# drive_circuit.net
KiCad netlist of a schematic drawn in Altium Designer
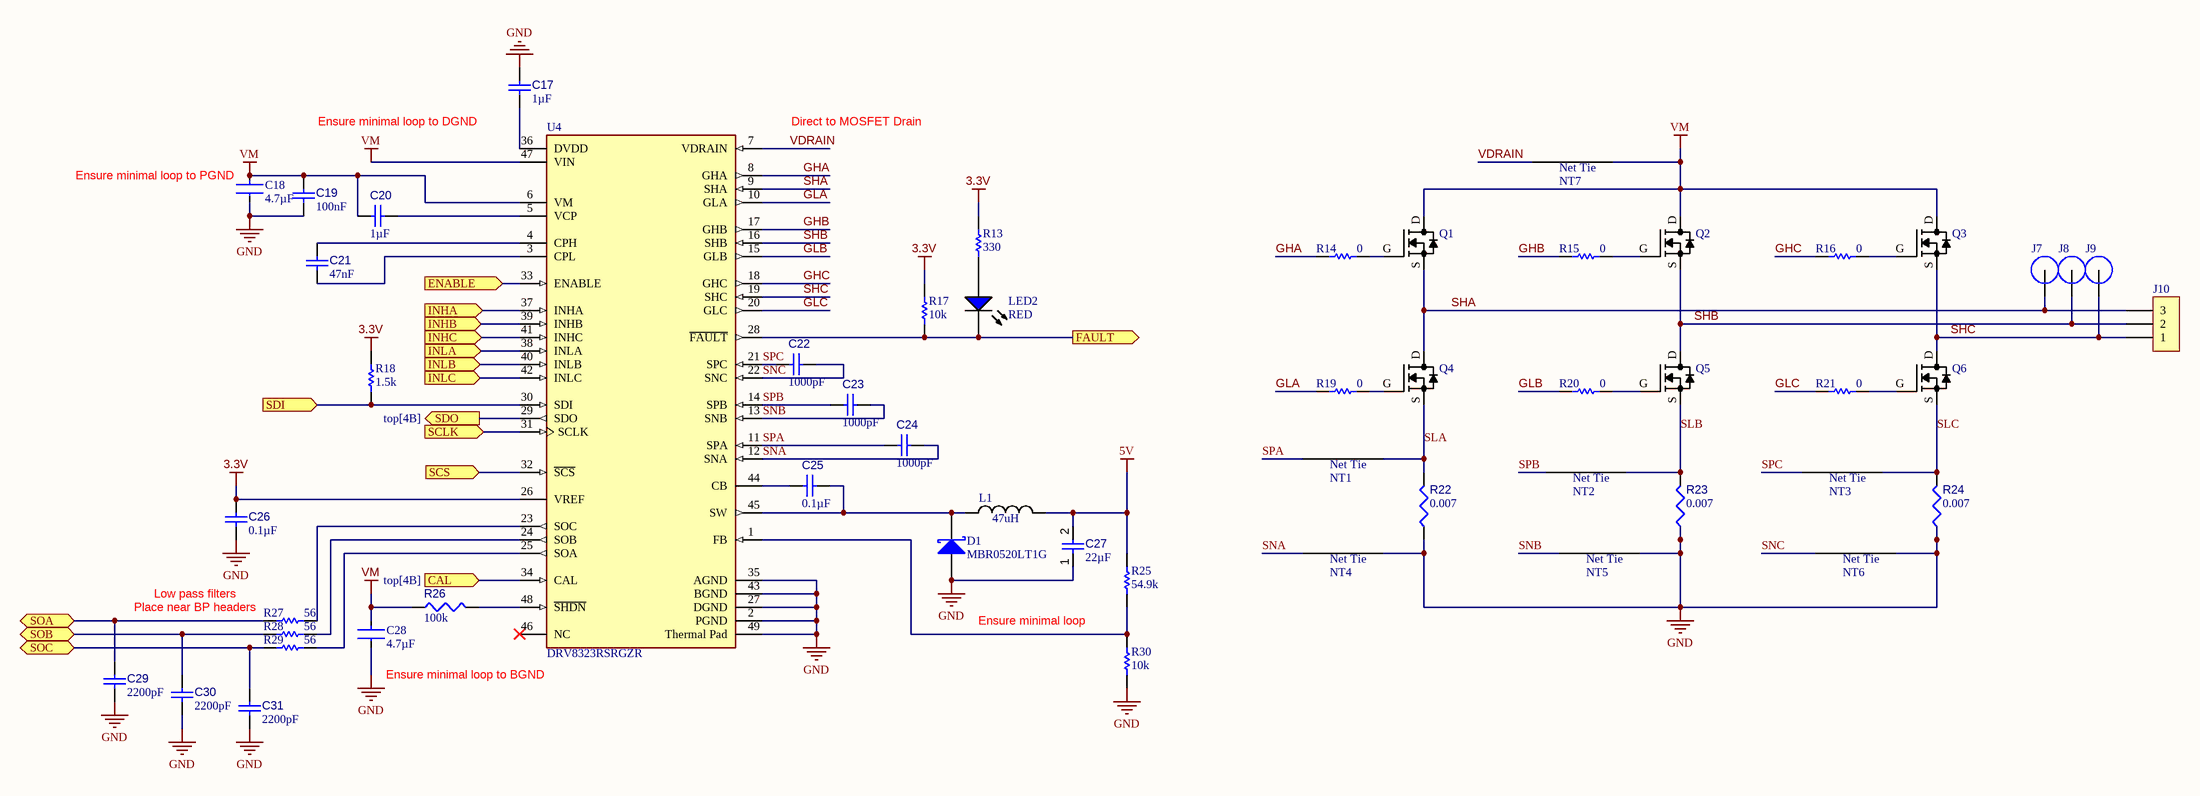
[diagram p0: drive_circuit.SchDoc]

(export (version "E")
  (design (tool "Eeschema 10.0.6"))
  (components
    (comp (ref "C17")
      (value "1µF")
      (footprint "CAPC1608X94X35NL15T15")
      (description "Chip Capacitor, 1 uF, +/- 10%, 6.3 V, 0603 (1608 Metric)")
      (fields (field (name "TOLERANCE") "10%") (field (name "Comment") "Capacitor 1 uF +/- 10% 16 V 0603"))
      (libsource (lib "bai yaohui") (part "CAP-NP-2"))
    )
    (comp (ref "C18")
      (value "4.7µF")
      (footprint "FP-MK325N-MFG")
      (fields (field (name "Comment") "HMK325B7225KN-T"))
      (libsource (lib "bai yaohui") (part "b4654b650e69147ec39a6b967a45e02"))
    )
    (comp (ref "C19")
      (value "100nF")
      (footprint "CAPC0603(1608)100_L")
      (description "Chip Capacitor, 4.7µF +/-20%, 100V, 0603, Thickness 1 mm")
      (fields (field (name "TOLERANCE") "10%") (field (name "Comment") "Capacitor 4.7µF +/-20% 10V 0603"))
      (libsource (lib "bai yaohui") (part "CAP-NP-2"))
    )
    (comp (ref "C20")
      (value "1µF")
      (footprint "CAPC1608X94X35NL15T15")
      (description "Chip Capacitor, 1 uF, +/- 10%, 16 V, 0603 (1608 Metric)")
      (fields (field (name "TOLERANCE") "10%") (field (name "Comment") "Capacitor 1 uF +/- 10% 16 V 0603"))
      (libsource (lib "bai yaohui") (part "CAP-NP-2"))
    )
    (comp (ref "C21")
      (value "47nF")
      (footprint "CAPC0603(1608)100_L")
      (description "Chip Capacitor, 47nF +/-20%, 100V, 0603, Thickness 1 mm")
      (fields (field (name "TOLERANCE") "10%") (field (name "Comment") "Capacitor 4.7µF +/-20% 10V 0603"))
      (libsource (lib "bai yaohui") (part "CAP-NP-2"))
    )
    (comp (ref "C22")
      (value "1000pF")
      (footprint "CAPC1608X94X35NL15T15")
      (description "Chip Capacitor, 0.1uF, +/- 10%, 6.3 V, 0603 (1608 Metric)")
      (fields (field (name "TOLERANCE") "10%") (field (name "Comment") "Capacitor 1 uF +/- 10% 16 V 0603"))
      (libsource (lib "bai yaohui") (part "CAP-NP-2"))
    )
    (comp (ref "C23")
      (value "1000pF")
      (footprint "CAPC1608X94X35NL15T15")
      (description "Chip Capacitor, 0.1uF, +/- 10%, 6.3 V, 0603 (1608 Metric)")
      (fields (field (name "TOLERANCE") "10%") (field (name "Comment") "Capacitor 1 uF +/- 10% 16 V 0603"))
      (libsource (lib "bai yaohui") (part "CAP-NP-2"))
    )
    (comp (ref "C24")
      (value "1000pF")
      (footprint "CAPC1608X94X35NL15T15")
      (description "Chip Capacitor, 0.1uF, +/- 10%, 6.3 V, 0603 (1608 Metric)")
      (fields (field (name "TOLERANCE") "10%") (field (name "Comment") "Capacitor 1 uF +/- 10% 16 V 0603"))
      (libsource (lib "bai yaohui") (part "CAP-NP-2"))
    )
    (comp (ref "C25")
      (value "0.1µF")
      (footprint "CAPC1608X94X35NL15T15")
      (description "Chip Capacitor, 0.1uF, +/- 10%, 6.3 V, 0603 (1608 Metric)")
      (fields (field (name "TOLERANCE") "10%") (field (name "Comment") "Capacitor 1 uF +/- 10% 16 V 0603"))
      (libsource (lib "bai yaohui") (part "CAP-NP-2"))
    )
    (comp (ref "C26")
      (value "0.1µF")
      (footprint "CAPC1608X94X35NL15T15")
      (description "Chip Capacitor, 0.1uF, +/- 10%, 6.3 V, 0603 (1608 Metric)")
      (fields (field (name "TOLERANCE") "10%") (field (name "Comment") "Capacitor 1 uF +/- 10% 16 V 0603"))
      (libsource (lib "bai yaohui") (part "CAP-NP-2"))
    )
    (comp (ref "C27")
      (value "22µF")
      (footprint "CAPC3216X180X50NL20T25")
      (description "Chip Capacitor, 22 uF, +/- 10%, 16 V, 1206 (3216 Metric)")
      (fields (field (name "TOLERANCE") "10%") (field (name "Comment") "Capacitor 10 uF +/- 10% 16 V 1206"))
      (libsource (lib "") (part "CAP-NP-2_1"))
    )
    (comp (ref "C28")
      (value "4.7µF")
      (footprint "FP-MK325N-MFG")
      (fields (field (name "Comment") "HMK325B7225KN-T"))
      (libsource (lib "bai yaohui") (part "b4654b650e69147ec39a6b967a45e02"))
    )
    (comp (ref "C29")
      (value "2200pF")
      (footprint "CAPC1608X94X35NL15T15")
      (description "Chip Capacitor, 0.1uF, +/- 10%, 6.3 V, 0603 (1608 Metric)")
      (fields (field (name "TOLERANCE") "10%") (field (name "Comment") "Capacitor 1 uF +/- 10% 16 V 0603"))
      (libsource (lib "bai yaohui") (part "CAP-NP-2"))
    )
    (comp (ref "C30")
      (value "2200pF")
      (footprint "CAPC1608X94X35NL15T15")
      (description "Chip Capacitor, 0.1uF, +/- 10%, 6.3 V, 0603 (1608 Metric)")
      (fields (field (name "TOLERANCE") "10%") (field (name "Comment") "Capacitor 1 uF +/- 10% 16 V 0603"))
      (libsource (lib "bai yaohui") (part "CAP-NP-2"))
    )
    (comp (ref "C31")
      (value "2200pF")
      (footprint "CAPC1608X94X35NL15T15")
      (description "Chip Capacitor, 0.1uF, +/- 10%, 6.3 V, 0603 (1608 Metric)")
      (fields (field (name "TOLERANCE") "10%") (field (name "Comment") "Capacitor 1 uF +/- 10% 16 V 0603"))
      (libsource (lib "bai yaohui") (part "CAP-NP-2"))
    )
    (comp (ref "D1")
      (value "MBR0520LT1G")
      (footprint "ONSC-SOD-123-2-425-04_V")
      (description "Schottky Power Rectifier, 20 V, 5.5 A, -65 to 125 degC, 2-Pin SMD, RoHS, Tape and Reel")
      (fields (field (name "MANUFACTURER") "ON Semiconductor"))
      (libsource (lib "bai yaohui") (part "DSKY-AK-2"))
    )
    (comp (ref "J7")
      (value "~")
      (footprint "M3 Spade Hole")
      (description "M3 Spade Terminal")
      (libsource (lib "CustomComponents") (part "M3 Spade Terminal"))
    )
    (comp (ref "J8")
      (value "~")
      (footprint "M3 Spade Hole")
      (description "M3 Spade Terminal")
      (libsource (lib "CustomComponents") (part "M3 Spade Terminal"))
    )
    (comp (ref "J9")
      (value "~")
      (footprint "M3 Spade Hole")
      (description "M3 Spade Terminal")
      (libsource (lib "CustomComponents") (part "M3 Spade Terminal"))
    )
    (comp (ref "J10")
      (value "1704936")
      (footprint "1704936")
      (description "CONN TERM BLOCK 3POS 7.62MM")
      (fields (field (name "MANUFACTURER") "Phoenix Contact") (field (name "VOLTAGE") "300V"))
      (libsource (lib "CustomComponents") (part "1704936"))
    )
    (comp (ref "L1")
      (value "47uH")
      (footprint "INDC6060X28N")
      (description "INDUCTOR 47UH 1.4A 175.5 MOHM")
      (fields (field (name "Comment") "22uH"))
      (libsource (lib "CustomComponents") (part "NR6028T220M"))
    )
    (comp (ref "LED2")
      (value "RED")
      (footprint "VISH-TLMX1100-2_V")
      (description "red LED, 10 mA, 2 V, -40 to 100 degC, 2-Pin SMD (0603), RoHS, Tape and Reel")
      (fields (field (name "POWER") "68mW") (field (name "MANUFACTURER") "Vishay Semiconductor"))
      (libsource (lib "bai yaohui") (part "LED-BLUE-AK-2"))
    )
    (comp (ref "NT1")
      (value "0.25mm")
      (footprint "CustomFootprints:NetTie_0.25mm")
      (libsource (lib "CustomComponents") (part "NetTie_0.25mm"))
    )
    (comp (ref "NT2")
      (value "0.25mm")
      (footprint "CustomFootprints:NetTie_0.25mm")
      (libsource (lib "CustomComponents") (part "NetTie_0.25mm"))
    )
    (comp (ref "NT3")
      (value "0.25mm")
      (footprint "CustomFootprints:NetTie_0.25mm")
      (libsource (lib "CustomComponents") (part "NetTie_0.25mm"))
    )
    (comp (ref "NT4")
      (value "0.25mm")
      (footprint "CustomFootprints:NetTie_0.25mm")
      (libsource (lib "CustomComponents") (part "NetTie_0.25mm"))
    )
    (comp (ref "NT5")
      (value "0.25mm")
      (footprint "CustomFootprints:NetTie_0.25mm")
      (libsource (lib "CustomComponents") (part "NetTie_0.25mm"))
    )
    (comp (ref "NT6")
      (value "0.25mm")
      (footprint "CustomFootprints:NetTie_0.25mm")
      (libsource (lib "CustomComponents") (part "NetTie_0.25mm"))
    )
    (comp (ref "NT7")
      (value "0.25mm")
      (footprint "CustomFootprints:NetTie_0.25mm")
      (libsource (lib "CustomComponents") (part "NetTie_0.25mm"))
    )
    (comp (ref "Q1")
      (value "~")
      (footprint "SO8FL")
      (description "MOSFET N-CH 30V 13A SO8FL")
      (fields
        (field (name "MANUFACTURER") "ON Semiconductor")
        (field (name "MANUFACTURER PART NUMBER") "NTMFS4935NT1G")
      )
      (libsource (lib "CustomComponents") (part "NTMFS4935NT1G"))
    )
    (comp (ref "Q2")
      (value "~")
      (footprint "SO8FL")
      (description "MOSFET N-CH 30V 13A SO8FL")
      (fields
        (field (name "MANUFACTURER") "ON Semiconductor")
        (field (name "MANUFACTURER PART NUMBER") "NTMFS4935NT1G")
      )
      (libsource (lib "CustomComponents") (part "NTMFS4935NT1G"))
    )
    (comp (ref "Q3")
      (value "~")
      (footprint "SO8FL")
      (description "MOSFET N-CH 30V 13A SO8FL")
      (fields
        (field (name "MANUFACTURER") "ON Semiconductor")
        (field (name "MANUFACTURER PART NUMBER") "NTMFS4935NT1G")
      )
      (libsource (lib "CustomComponents") (part "NTMFS4935NT1G"))
    )
    (comp (ref "Q4")
      (value "~")
      (footprint "SO8FL")
      (description "MOSFET N-CH 30V 13A SO8FL")
      (fields
        (field (name "MANUFACTURER") "ON Semiconductor")
        (field (name "MANUFACTURER PART NUMBER") "NTMFS4935NT1G")
      )
      (libsource (lib "CustomComponents") (part "NTMFS4935NT1G"))
    )
    (comp (ref "Q5")
      (value "~")
      (footprint "SO8FL")
      (description "MOSFET N-CH 30V 13A SO8FL")
      (fields
        (field (name "MANUFACTURER") "ON Semiconductor")
        (field (name "MANUFACTURER PART NUMBER") "NTMFS4935NT1G")
      )
      (libsource (lib "CustomComponents") (part "NTMFS4935NT1G"))
    )
    (comp (ref "Q6")
      (value "~")
      (footprint "SO8FL")
      (description "MOSFET N-CH 30V 13A SO8FL")
      (fields
        (field (name "MANUFACTURER") "ON Semiconductor")
        (field (name "MANUFACTURER PART NUMBER") "NTMFS4935NT1G")
      )
      (libsource (lib "CustomComponents") (part "NTMFS4935NT1G"))
    )
    (comp (ref "R13")
      (value "330")
      (footprint "RESC1608X55X25ML10T15")
      (description "Chip Resistor, 330 Ohm, 0.1 W, -55 to 155 degC, 0603 (1608 Metric)")
      (fields (field (name "POWER") "100mW") (field (name "TOLERANCE") "5%"))
      (libsource (lib "") (part "RES-2_1"))
    )
    (comp (ref "R14")
      (value "0")
      (footprint "RESC1608X55X25ML10T15")
      (description "Chip Resistor, 10k Ohm, 0.1 W, -55 to 155 degC, 0603 (1608 Metric)")
      (fields (field (name "POWER") "100mW") (field (name "TOLERANCE") "5%"))
      (libsource (lib "") (part "RES-2_1"))
    )
    (comp (ref "R15")
      (value "0")
      (footprint "RESC1608X55X25ML10T15")
      (description "Chip Resistor, 10k Ohm, 0.1 W, -55 to 155 degC, 0603 (1608 Metric)")
      (fields (field (name "POWER") "100mW") (field (name "TOLERANCE") "5%"))
      (libsource (lib "") (part "RES-2_1"))
    )
    (comp (ref "R16")
      (value "0")
      (footprint "RESC1608X55X25ML10T15")
      (description "Chip Resistor, 10k Ohm, 0.1 W, -55 to 155 degC, 0603 (1608 Metric)")
      (fields (field (name "POWER") "100mW") (field (name "TOLERANCE") "5%"))
      (libsource (lib "") (part "RES-2_1"))
    )
    (comp (ref "R17")
      (value "10k")
      (footprint "RESC1608X55X25ML10T15")
      (description "Chip Resistor, 10k Ohm, 0.1 W, -55 to 155 degC, 0603 (1608 Metric)")
      (fields (field (name "POWER") "100mW") (field (name "TOLERANCE") "5%"))
      (libsource (lib "") (part "RES-2_1"))
    )
    (comp (ref "R18")
      (value "1.5k")
      (footprint "RESC1608X55X25ML10T15")
      (description "Chip Resistor, 1.5k Ohm, 0.1 W, -55 to 155 degC, 0603 (1608 Metric)")
      (fields (field (name "POWER") "100mW") (field (name "TOLERANCE") "5%"))
      (libsource (lib "") (part "RES-2_1"))
    )
    (comp (ref "R19")
      (value "0")
      (footprint "RESC1608X55X25ML10T15")
      (description "Chip Resistor, 10k Ohm, 0.1 W, -55 to 155 degC, 0603 (1608 Metric)")
      (fields (field (name "POWER") "100mW") (field (name "TOLERANCE") "5%"))
      (libsource (lib "") (part "RES-2_1"))
    )
    (comp (ref "R20")
      (value "0")
      (footprint "RESC1608X55X25ML10T15")
      (description "Chip Resistor, 10k Ohm, 0.1 W, -55 to 155 degC, 0603 (1608 Metric)")
      (fields (field (name "POWER") "100mW") (field (name "TOLERANCE") "5%"))
      (libsource (lib "") (part "RES-2_1"))
    )
    (comp (ref "R21")
      (value "0")
      (footprint "RESC1608X55X25ML10T15")
      (description "Chip Resistor, 10k Ohm, 0.1 W, -55 to 155 degC, 0603 (1608 Metric)")
      (fields (field (name "POWER") "100mW") (field (name "TOLERANCE") "5%"))
      (libsource (lib "") (part "RES-2_1"))
    )
    (comp (ref "R22")
      (value "0.007")
      (footprint "FP-RT2512-MFG")
      (description "Fixed Resistor, Thin Film, 0.75W, 1210ohm, 200V, 0.1% +/-Tol, 25ppm/Cel, Surface Mount, 2512")
      (fields (field (name "POWER") "750mW") (field (name "TOLERANCE") "0.1%"))
      (libsource (lib "bai yaohui") (part "RES-2"))
    )
    (comp (ref "R23")
      (value "0.007")
      (footprint "FP-RT2512-MFG")
      (description "Fixed Resistor, Thin Film, 0.75W, 1210ohm, 200V, 0.1% +/-Tol, 25ppm/Cel, Surface Mount, 2512")
      (fields (field (name "POWER") "750mW") (field (name "TOLERANCE") "0.1%"))
      (libsource (lib "bai yaohui") (part "RES-2"))
    )
    (comp (ref "R24")
      (value "0.007")
      (footprint "FP-RT2512-MFG")
      (description "Fixed Resistor, Thin Film, 0.75W, 1210ohm, 200V, 0.1% +/-Tol, 25ppm/Cel, Surface Mount, 2512")
      (fields (field (name "POWER") "750mW") (field (name "TOLERANCE") "0.1%"))
      (libsource (lib "bai yaohui") (part "RES-2"))
    )
    (comp (ref "R25")
      (value "54.9k")
      (footprint "RESC1608X55X25ML10T15")
      (description "Chip Resistor, 10k Ohm, 0.1 W, -55 to 155 degC, 0603 (1608 Metric)")
      (fields (field (name "POWER") "100mW") (field (name "TOLERANCE") "5%"))
      (libsource (lib "") (part "RES-2_1"))
    )
    (comp (ref "R26")
      (value "100k")
      (footprint "RESC1608X55X25ML10T15")
      (description "Chip Resistor, 100 KOhm, +/- 1%, 0.1 W, -55 to 155 degC, 0603 (1608 Metric)")
      (fields (field (name "TOLERANCE") "1%") (field (name "POWER") "100mW"))
      (libsource (lib "bai yaohui") (part "RES-2"))
    )
    (comp (ref "R27")
      (value "56")
      (footprint "RESC1608X55X25ML10T15")
      (description "Chip Resistor, 10k Ohm, 0.1 W, -55 to 155 degC, 0603 (1608 Metric)")
      (fields (field (name "POWER") "100mW") (field (name "TOLERANCE") "5%"))
      (libsource (lib "") (part "RES-2_1"))
    )
    (comp (ref "R28")
      (value "56")
      (footprint "RESC1608X55X25ML10T15")
      (description "Chip Resistor, 10k Ohm, 0.1 W, -55 to 155 degC, 0603 (1608 Metric)")
      (fields (field (name "POWER") "100mW") (field (name "TOLERANCE") "5%"))
      (libsource (lib "") (part "RES-2_1"))
    )
    (comp (ref "R29")
      (value "56")
      (footprint "RESC1608X55X25ML10T15")
      (description "Chip Resistor, 10k Ohm, 0.1 W, -55 to 155 degC, 0603 (1608 Metric)")
      (fields (field (name "POWER") "100mW") (field (name "TOLERANCE") "5%"))
      (libsource (lib "") (part "RES-2_1"))
    )
    (comp (ref "R30")
      (value "10k")
      (footprint "RESC1608X55X25ML10T15")
      (description "Chip Resistor, 10k Ohm, 0.1 W, -55 to 155 degC, 0603 (1608 Metric)")
      (fields (field (name "POWER") "100mW") (field (name "TOLERANCE") "5%"))
      (libsource (lib "") (part "RES-2_1"))
    )
    (comp (ref "U4")
      (value "DRV8323RSRGZR")
      (footprint "FP-RGZ0048A-IPC_A")
      (description "Brushless DC Motor Controller, 0.005A, PQCC48")
      (libsource (lib "bai yaohui") (part "9f6f2f4cce60835f155f5fba280b04a"))
    )
  )
  (nets
    (net (code "1") (name "/CAL") (class "Default")
      (node (ref "U4") (pin "34") (pinfunction "CAL_34") (pintype "input"))
    )
    (net (code "2") (name "/ENABLE") (class "Default")
      (node (ref "U4") (pin "33") (pinfunction "ENABLE_33") (pintype "input"))
    )
    (net (code "3") (name "/FAULT") (class "Default")
      (node (ref "LED2") (pin "2") (pinfunction "K_2") (pintype "passive"))
      (node (ref "R17") (pin "1") (pinfunction "1_1") (pintype "passive"))
      (node (ref "U4") (pin "28") (pinfunction "~{FAULT}_28") (pintype "output"))
    )
    (net (code "4") (name "/GHA") (class "Default")
      (node (ref "R14") (pin "2") (pinfunction "2_2") (pintype "passive"))
      (node (ref "U4") (pin "8") (pinfunction "GHA_8") (pintype "output"))
    )
    (net (code "5") (name "/GHB") (class "Default")
      (node (ref "R15") (pin "2") (pinfunction "2_2") (pintype "passive"))
      (node (ref "U4") (pin "17") (pinfunction "GHB_17") (pintype "output"))
    )
    (net (code "6") (name "/GHC") (class "Default")
      (node (ref "R16") (pin "2") (pinfunction "2_2") (pintype "passive"))
      (node (ref "U4") (pin "18") (pinfunction "GHC_18") (pintype "output"))
    )
    (net (code "7") (name "/GLA") (class "Default")
      (node (ref "R19") (pin "2") (pinfunction "2_2") (pintype "passive"))
      (node (ref "U4") (pin "10") (pinfunction "GLA_10") (pintype "output"))
    )
    (net (code "8") (name "/GLB") (class "Default")
      (node (ref "R20") (pin "2") (pinfunction "2_2") (pintype "passive"))
      (node (ref "U4") (pin "15") (pinfunction "GLB_15") (pintype "output"))
    )
    (net (code "9") (name "/GLC") (class "Default")
      (node (ref "R21") (pin "2") (pinfunction "2_2") (pintype "passive"))
      (node (ref "U4") (pin "20") (pinfunction "GLC_20") (pintype "output"))
    )
    (net (code "10") (name "/INHA") (class "Default")
      (node (ref "U4") (pin "37") (pinfunction "INHA_37") (pintype "input"))
    )
    (net (code "11") (name "/INHB") (class "Default")
      (node (ref "U4") (pin "39") (pinfunction "INHB_39") (pintype "input"))
    )
    (net (code "12") (name "/INHC") (class "Default")
      (node (ref "U4") (pin "41") (pinfunction "INHC_41") (pintype "input"))
    )
    (net (code "13") (name "/INLA") (class "Default")
      (node (ref "U4") (pin "38") (pinfunction "INLA_38") (pintype "input"))
    )
    (net (code "14") (name "/INLB") (class "Default")
      (node (ref "U4") (pin "40") (pinfunction "INLB_40") (pintype "input"))
    )
    (net (code "15") (name "/INLC") (class "Default")
      (node (ref "U4") (pin "42") (pinfunction "INLC_42") (pintype "input"))
    )
    (net (code "16") (name "/SCLK") (class "Default")
      (node (ref "U4") (pin "31") (pinfunction "SCLK_31") (pintype "input"))
    )
    (net (code "17") (name "/SCS") (class "Default")
      (node (ref "U4") (pin "32") (pinfunction "~{SCS}_32") (pintype "input"))
    )
    (net (code "18") (name "/SDI") (class "Default")
      (node (ref "R18") (pin "1") (pinfunction "1_1") (pintype "passive"))
      (node (ref "U4") (pin "30") (pinfunction "SDI_30") (pintype "input"))
    )
    (net (code "19") (name "/SDO") (class "Default")
      (node (ref "U4") (pin "29") (pinfunction "SDO_29") (pintype "output"))
    )
    (net (code "20") (name "/SHA") (class "Default")
      (node (ref "J10") (pin "3") (pinfunction "3_3") (pintype "passive"))
      (node (ref "J7") (pin "1") (pinfunction "1_1") (pintype "passive"))
      (node (ref "Q1") (pin "S") (pinfunction "S_S") (pintype "passive"))
      (node (ref "Q4") (pin "D") (pinfunction "D_D") (pintype "passive"))
      (node (ref "U4") (pin "9") (pinfunction "SHA_9") (pintype "input"))
    )
    (net (code "21") (name "/SHB") (class "Default")
      (node (ref "J10") (pin "2") (pinfunction "2_2") (pintype "passive"))
      (node (ref "J8") (pin "1") (pinfunction "1_1") (pintype "passive"))
      (node (ref "Q2") (pin "S") (pinfunction "S_S") (pintype "passive"))
      (node (ref "Q5") (pin "D") (pinfunction "D_D") (pintype "passive"))
      (node (ref "U4") (pin "16") (pinfunction "SHB_16") (pintype "input"))
    )
    (net (code "22") (name "/SHC") (class "Default")
      (node (ref "J10") (pin "1") (pinfunction "1_1") (pintype "passive"))
      (node (ref "J9") (pin "1") (pinfunction "1_1") (pintype "passive"))
      (node (ref "Q3") (pin "S") (pinfunction "S_S") (pintype "passive"))
      (node (ref "Q6") (pin "D") (pinfunction "D_D") (pintype "passive"))
      (node (ref "U4") (pin "19") (pinfunction "SHC_19") (pintype "input"))
    )
    (net (code "23") (name "/SLA") (class "Default")
      (node (ref "NT1") (pin "2") (pintype "passive"))
      (node (ref "Q4") (pin "S") (pinfunction "S_S") (pintype "passive"))
      (node (ref "R22") (pin "2") (pinfunction "2_2") (pintype "passive"))
    )
    (net (code "24") (name "/SLB") (class "Default")
      (node (ref "NT2") (pin "2") (pintype "passive"))
      (node (ref "Q5") (pin "S") (pinfunction "S_S") (pintype "passive"))
      (node (ref "R23") (pin "2") (pinfunction "2_2") (pintype "passive"))
    )
    (net (code "25") (name "/SLC") (class "Default")
      (node (ref "NT3") (pin "2") (pintype "passive"))
      (node (ref "Q6") (pin "S") (pinfunction "S_S") (pintype "passive"))
      (node (ref "R24") (pin "2") (pinfunction "2_2") (pintype "passive"))
    )
    (net (code "26") (name "/SNA") (class "Default")
      (node (ref "C24") (pin "1") (pinfunction "1_1") (pintype "passive"))
      (node (ref "NT4") (pin "1") (pintype "passive"))
      (node (ref "U4") (pin "12") (pinfunction "SNA_12") (pintype "input"))
    )
    (net (code "27") (name "/SNB") (class "Default")
      (node (ref "C23") (pin "1") (pinfunction "1_1") (pintype "passive"))
      (node (ref "NT5") (pin "1") (pintype "passive"))
      (node (ref "U4") (pin "13") (pinfunction "SNB_13") (pintype "input"))
    )
    (net (code "28") (name "/SNC") (class "Default")
      (node (ref "C22") (pin "1") (pinfunction "1_1") (pintype "passive"))
      (node (ref "NT6") (pin "1") (pintype "passive"))
      (node (ref "U4") (pin "22") (pinfunction "SNC_22") (pintype "input"))
    )
    (net (code "29") (name "/SOA") (class "Default")
      (node (ref "C29") (pin "2") (pinfunction "2_2") (pintype "passive"))
      (node (ref "R27") (pin "2") (pinfunction "2_2") (pintype "passive"))
    )
    (net (code "30") (name "/SOB") (class "Default")
      (node (ref "C30") (pin "2") (pinfunction "2_2") (pintype "passive"))
      (node (ref "R28") (pin "2") (pinfunction "2_2") (pintype "passive"))
    )
    (net (code "31") (name "/SOC") (class "Default")
      (node (ref "C31") (pin "2") (pinfunction "2_2") (pintype "passive"))
      (node (ref "R29") (pin "2") (pinfunction "2_2") (pintype "passive"))
    )
    (net (code "32") (name "/SPA") (class "Default")
      (node (ref "C24") (pin "2") (pinfunction "2_2") (pintype "passive"))
      (node (ref "NT1") (pin "1") (pintype "passive"))
      (node (ref "U4") (pin "11") (pinfunction "SPA_11") (pintype "input"))
    )
    (net (code "33") (name "/SPB") (class "Default")
      (node (ref "C23") (pin "2") (pinfunction "2_2") (pintype "passive"))
      (node (ref "NT2") (pin "1") (pintype "passive"))
      (node (ref "U4") (pin "14") (pinfunction "SPB_14") (pintype "input"))
    )
    (net (code "34") (name "/SPC") (class "Default")
      (node (ref "C22") (pin "2") (pinfunction "2_2") (pintype "passive"))
      (node (ref "NT3") (pin "1") (pintype "passive"))
      (node (ref "U4") (pin "21") (pinfunction "SPC_21") (pintype "input"))
    )
    (net (code "35") (name "/VDRAIN") (class "Default")
      (node (ref "NT7") (pin "1") (pintype "passive"))
      (node (ref "U4") (pin "7") (pinfunction "VDRAIN_7") (pintype "input"))
    )
    (net (code "36") (name "3.3V") (class "Default")
      (node (ref "C26") (pin "2") (pinfunction "2_2") (pintype "passive"))
      (node (ref "R13") (pin "2") (pinfunction "2_2") (pintype "passive"))
      (node (ref "R17") (pin "2") (pinfunction "2_2") (pintype "passive"))
      (node (ref "R18") (pin "2") (pinfunction "2_2") (pintype "passive"))
      (node (ref "U4") (pin "26") (pinfunction "VREF_26") (pintype "power_in"))
    )
    (net (code "37") (name "5V") (class "Default")
      (node (ref "C27") (pin "2") (pinfunction "2_2") (pintype "passive"))
      (node (ref "L1") (pin "2") (pinfunction "2_2") (pintype "passive"))
      (node (ref "R25") (pin "2") (pinfunction "2_2") (pintype "passive"))
    )
    (net (code "38") (name "GND") (class "Default")
      (node (ref "C17") (pin "2") (pinfunction "2_2") (pintype "passive"))
      (node (ref "C18") (pin "2") (pinfunction "2_2") (pintype "passive"))
      (node (ref "C19") (pin "1") (pinfunction "1_1") (pintype "passive"))
      (node (ref "C26") (pin "1") (pinfunction "1_1") (pintype "passive"))
      (node (ref "C27") (pin "1") (pinfunction "1_1") (pintype "passive"))
      (node (ref "C28") (pin "2") (pinfunction "2_2") (pintype "passive"))
      (node (ref "C29") (pin "1") (pinfunction "1_1") (pintype "passive"))
      (node (ref "C30") (pin "1") (pinfunction "1_1") (pintype "passive"))
      (node (ref "C31") (pin "1") (pinfunction "1_1") (pintype "passive"))
      (node (ref "D1") (pin "1") (pinfunction "A_1") (pintype "passive"))
      (node (ref "NT4") (pin "2") (pintype "passive"))
      (node (ref "NT5") (pin "2") (pintype "passive"))
      (node (ref "NT6") (pin "2") (pintype "passive"))
      (node (ref "R22") (pin "1") (pinfunction "1_1") (pintype "passive"))
      (node (ref "R23") (pin "1") (pinfunction "1_1") (pintype "passive"))
      (node (ref "R24") (pin "1") (pinfunction "1_1") (pintype "passive"))
      (node (ref "R30") (pin "1") (pinfunction "1_1") (pintype "passive"))
      (node (ref "U4") (pin "2") (pinfunction "PGND_2") (pintype "power_in"))
      (node (ref "U4") (pin "27") (pinfunction "DGND_27") (pintype "power_in"))
      (node (ref "U4") (pin "35") (pinfunction "AGND_35") (pintype "power_in"))
      (node (ref "U4") (pin "43") (pinfunction "BGND_43") (pintype "power_in"))
      (node (ref "U4") (pin "49") (pinfunction "Thermal_Pad_49") (pintype "power_in"))
    )
    (net (code "39") (name "Net-(D1-K)") (class "Default")
      (node (ref "C25") (pin "1") (pinfunction "1_1") (pintype "passive"))
      (node (ref "D1") (pin "2") (pinfunction "K_2") (pintype "passive"))
      (node (ref "L1") (pin "1") (pinfunction "1_1") (pintype "passive"))
      (node (ref "U4") (pin "45") (pinfunction "SW_45") (pintype "output"))
    )
    (net (code "40") (name "Net-(LED2-A)") (class "Default")
      (node (ref "LED2") (pin "1") (pinfunction "A_1") (pintype "passive"))
      (node (ref "R13") (pin "1") (pinfunction "1_1") (pintype "passive"))
    )
    (net (code "41") (name "Net-(Q1-PadG)") (class "Default")
      (node (ref "Q1") (pin "G") (pinfunction "G_G") (pintype "passive"))
      (node (ref "R14") (pin "1") (pinfunction "1_1") (pintype "passive"))
    )
    (net (code "42") (name "Net-(Q2-PadG)") (class "Default")
      (node (ref "Q2") (pin "G") (pinfunction "G_G") (pintype "passive"))
      (node (ref "R15") (pin "1") (pinfunction "1_1") (pintype "passive"))
    )
    (net (code "43") (name "Net-(Q3-PadG)") (class "Default")
      (node (ref "Q3") (pin "G") (pinfunction "G_G") (pintype "passive"))
      (node (ref "R16") (pin "1") (pinfunction "1_1") (pintype "passive"))
    )
    (net (code "44") (name "Net-(Q4-PadG)") (class "Default")
      (node (ref "Q4") (pin "G") (pinfunction "G_G") (pintype "passive"))
      (node (ref "R19") (pin "1") (pinfunction "1_1") (pintype "passive"))
    )
    (net (code "45") (name "Net-(Q5-PadG)") (class "Default")
      (node (ref "Q5") (pin "G") (pinfunction "G_G") (pintype "passive"))
      (node (ref "R20") (pin "1") (pinfunction "1_1") (pintype "passive"))
    )
    (net (code "46") (name "Net-(Q6-PadG)") (class "Default")
      (node (ref "Q6") (pin "G") (pinfunction "G_G") (pintype "passive"))
      (node (ref "R21") (pin "1") (pinfunction "1_1") (pintype "passive"))
    )
    (net (code "47") (name "Net-(U4-CB)") (class "Default")
      (node (ref "C25") (pin "2") (pinfunction "2_2") (pintype "passive"))
      (node (ref "U4") (pin "44") (pinfunction "CB_44") (pintype "power_in"))
    )
    (net (code "48") (name "Net-(U4-CPH)") (class "Default")
      (node (ref "C21") (pin "1") (pinfunction "1_1") (pintype "passive"))
      (node (ref "U4") (pin "4") (pinfunction "CPH_4") (pintype "power_in"))
    )
    (net (code "49") (name "Net-(U4-CPL)") (class "Default")
      (node (ref "C21") (pin "2") (pinfunction "2_2") (pintype "passive"))
      (node (ref "U4") (pin "3") (pinfunction "CPL_3") (pintype "power_in"))
    )
    (net (code "50") (name "Net-(U4-DVDD)") (class "Default")
      (node (ref "C17") (pin "1") (pinfunction "1_1") (pintype "passive"))
      (node (ref "U4") (pin "36") (pinfunction "DVDD_36") (pintype "power_in"))
    )
    (net (code "51") (name "Net-(U4-FB)") (class "Default")
      (node (ref "R25") (pin "1") (pinfunction "1_1") (pintype "passive"))
      (node (ref "R30") (pin "2") (pinfunction "2_2") (pintype "passive"))
      (node (ref "U4") (pin "1") (pinfunction "FB_1") (pintype "input"))
    )
    (net (code "52") (name "Net-(U4-SOA)") (class "Default")
      (node (ref "R29") (pin "1") (pinfunction "1_1") (pintype "passive"))
      (node (ref "U4") (pin "25") (pinfunction "SOA_25") (pintype "output"))
    )
    (net (code "53") (name "Net-(U4-SOB)") (class "Default")
      (node (ref "R28") (pin "1") (pinfunction "1_1") (pintype "passive"))
      (node (ref "U4") (pin "24") (pinfunction "SOB_24") (pintype "output"))
    )
    (net (code "54") (name "Net-(U4-SOC)") (class "Default")
      (node (ref "R27") (pin "1") (pinfunction "1_1") (pintype "passive"))
      (node (ref "U4") (pin "23") (pinfunction "SOC_23") (pintype "output"))
    )
    (net (code "55") (name "Net-(U4-VCP)") (class "Default")
      (node (ref "C20") (pin "2") (pinfunction "2_2") (pintype "passive"))
      (node (ref "U4") (pin "5") (pinfunction "VCP_5") (pintype "power_in"))
    )
    (net (code "56") (name "Net-(U4-~{SHDN})") (class "Default")
      (node (ref "R26") (pin "2") (pinfunction "2_2") (pintype "passive"))
      (node (ref "U4") (pin "48") (pinfunction "~{SHDN}_48") (pintype "input"))
    )
    (net (code "57") (name "VM") (class "Default")
      (node (ref "C18") (pin "1") (pinfunction "1_1") (pintype "passive"))
      (node (ref "C19") (pin "2") (pinfunction "2_2") (pintype "passive"))
      (node (ref "C20") (pin "1") (pinfunction "1_1") (pintype "passive"))
      (node (ref "C28") (pin "1") (pinfunction "1_1") (pintype "passive"))
      (node (ref "NT7") (pin "2") (pintype "passive"))
      (node (ref "Q1") (pin "D") (pinfunction "D_D") (pintype "passive"))
      (node (ref "Q2") (pin "D") (pinfunction "D_D") (pintype "passive"))
      (node (ref "Q3") (pin "D") (pinfunction "D_D") (pintype "passive"))
      (node (ref "R26") (pin "1") (pinfunction "1_1") (pintype "passive"))
      (node (ref "U4") (pin "47") (pinfunction "VIN_47") (pintype "power_in"))
      (node (ref "U4") (pin "6") (pinfunction "VM_6") (pintype "power_in"))
    )
    (net (code "58") (name "unconnected-(U4-NC-Pad46)") (class "Default")
      (node (ref "U4") (pin "46") (pinfunction "NC_46") (pintype "passive+no_connect"))
    )
  )
)
